# Modular_BO.net
KiCad netlist of a schematic drawn in Altium Designer
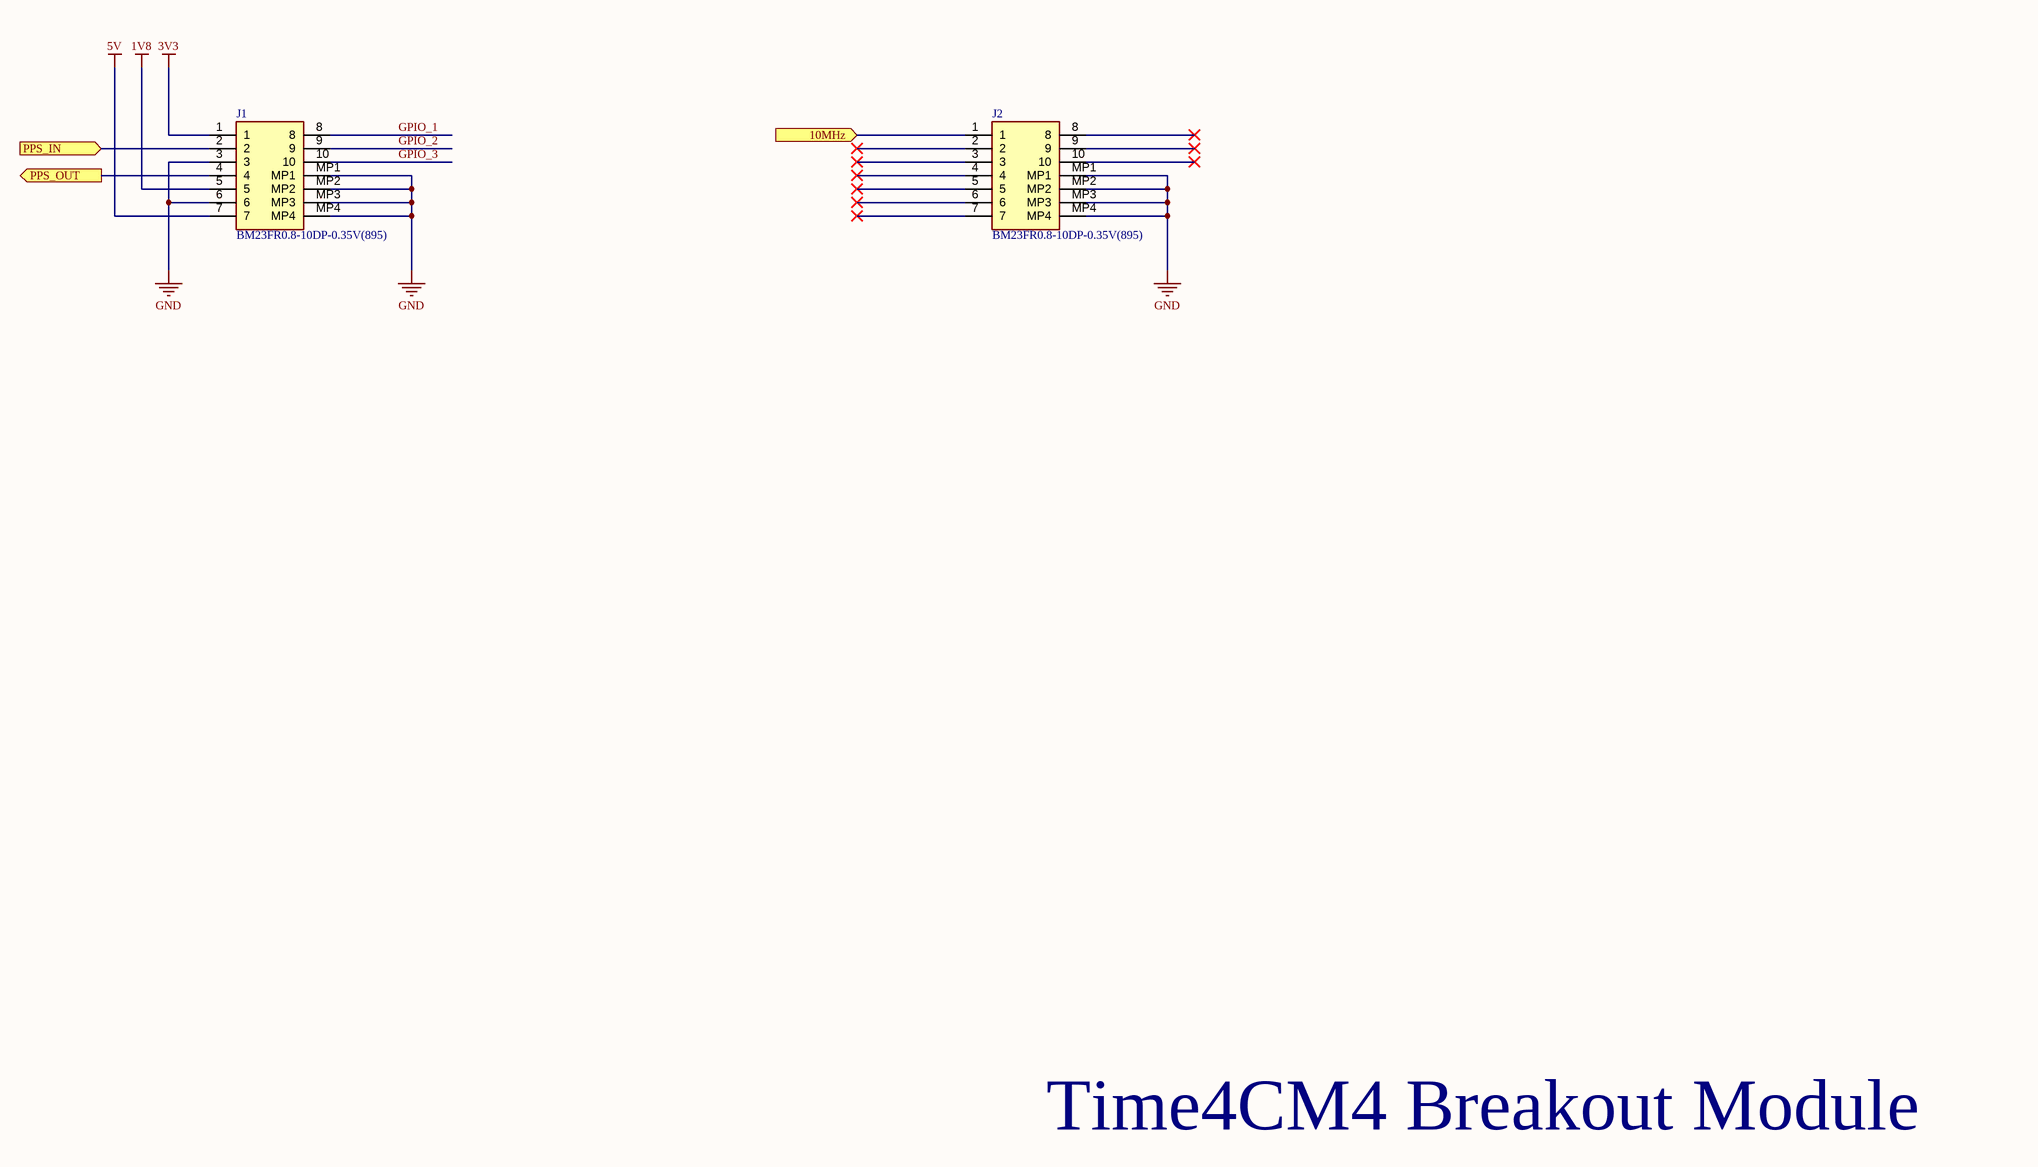
[diagram p0: Modular_BO.SchDoc]

(export (version "E")
  (design (tool "Eeschema 10.0.6"))
  (components
    (comp (ref "J1")
      (value "BM23FR0.8-10DP-0.35V(895)")
      (footprint "SamacSys:BM23FR0810DP035V895")
      (description "Connector")
      (fields
        (field (name "MANUFACTURER_PART_NUMBER") "BM23FR0.8-10DS-0.35V(895)")
        (field (name "MOUSER PART NUMBER") "798-3FR0810DS035V895")
      )
      (libsource (lib "*") (part "BM23FR0.8-10DS-0.35V_895_"))
    )
    (comp (ref "J2")
      (value "BM23FR0.8-10DP-0.35V(895)")
      (footprint "SamacSys:BM23FR0810DP035V895")
      (description "Connector")
      (fields
        (field (name "MANUFACTURER_PART_NUMBER") "BM23FR0.8-10DS-0.35V(895)")
        (field (name "MOUSER PART NUMBER") "798-3FR0810DS035V895")
      )
      (libsource (lib "*") (part "BM23FR0.8-10DS-0.35V_895_"))
    )
  )
  (nets
    (net (code "1") (name "/10MHz") (class "Default")
      (node (ref "J2") (pin "1") (pinfunction "1_1") (pintype "passive"))
    )
    (net (code "2") (name "/GPIO_1") (class "Default")
      (node (ref "J1") (pin "8") (pinfunction "8_8") (pintype "passive"))
    )
    (net (code "3") (name "/GPIO_2") (class "Default")
      (node (ref "J1") (pin "9") (pinfunction "9_9") (pintype "passive"))
    )
    (net (code "4") (name "/GPIO_3") (class "Default")
      (node (ref "J1") (pin "10") (pinfunction "10_10") (pintype "passive"))
    )
    (net (code "5") (name "/PPS_IN") (class "Default")
      (node (ref "J1") (pin "2") (pinfunction "2_2") (pintype "passive"))
    )
    (net (code "6") (name "/PPS_OUT") (class "Default")
      (node (ref "J1") (pin "4") (pinfunction "4_4") (pintype "passive"))
    )
    (net (code "7") (name "1V8") (class "Default")
      (node (ref "J1") (pin "5") (pinfunction "5_5") (pintype "passive"))
    )
    (net (code "8") (name "3V3") (class "Default")
      (node (ref "J1") (pin "1") (pinfunction "1_1") (pintype "passive"))
    )
    (net (code "9") (name "5V") (class "Default")
      (node (ref "J1") (pin "7") (pinfunction "7_7") (pintype "passive"))
    )
    (net (code "10") (name "GND") (class "Default")
      (node (ref "J1") (pin "3") (pinfunction "3_3") (pintype "passive"))
      (node (ref "J1") (pin "6") (pinfunction "6_6") (pintype "passive"))
      (node (ref "J1") (pin "MP1") (pinfunction "MP1_MP1") (pintype "passive"))
      (node (ref "J1") (pin "MP2") (pinfunction "MP2_MP2") (pintype "passive"))
      (node (ref "J1") (pin "MP3") (pinfunction "MP3_MP3") (pintype "passive"))
      (node (ref "J1") (pin "MP4") (pinfunction "MP4_MP4") (pintype "passive"))
      (node (ref "J2") (pin "MP1") (pinfunction "MP1_MP1") (pintype "passive"))
      (node (ref "J2") (pin "MP2") (pinfunction "MP2_MP2") (pintype "passive"))
      (node (ref "J2") (pin "MP3") (pinfunction "MP3_MP3") (pintype "passive"))
      (node (ref "J2") (pin "MP4") (pinfunction "MP4_MP4") (pintype "passive"))
    )
    (net (code "11") (name "unconnected-(J2-Pad2)") (class "Default")
      (node (ref "J2") (pin "2") (pinfunction "2_2") (pintype "passive+no_connect"))
    )
    (net (code "12") (name "unconnected-(J2-Pad3)") (class "Default")
      (node (ref "J2") (pin "3") (pinfunction "3_3") (pintype "passive+no_connect"))
    )
    (net (code "13") (name "unconnected-(J2-Pad4)") (class "Default")
      (node (ref "J2") (pin "4") (pinfunction "4_4") (pintype "passive+no_connect"))
    )
    (net (code "14") (name "unconnected-(J2-Pad5)") (class "Default")
      (node (ref "J2") (pin "5") (pinfunction "5_5") (pintype "passive+no_connect"))
    )
    (net (code "15") (name "unconnected-(J2-Pad6)") (class "Default")
      (node (ref "J2") (pin "6") (pinfunction "6_6") (pintype "passive+no_connect"))
    )
    (net (code "16") (name "unconnected-(J2-Pad7)") (class "Default")
      (node (ref "J2") (pin "7") (pinfunction "7_7") (pintype "passive+no_connect"))
    )
    (net (code "17") (name "unconnected-(J2-Pad8)") (class "Default")
      (node (ref "J2") (pin "8") (pinfunction "8_8") (pintype "passive+no_connect"))
    )
    (net (code "18") (name "unconnected-(J2-Pad9)") (class "Default")
      (node (ref "J2") (pin "9") (pinfunction "9_9") (pintype "passive+no_connect"))
    )
    (net (code "19") (name "unconnected-(J2-Pad10)") (class "Default")
      (node (ref "J2") (pin "10") (pinfunction "10_10") (pintype "passive+no_connect"))
    )
  )
)
